# 05_RTC.net
KiCad netlist of a schematic drawn in Altium Designer
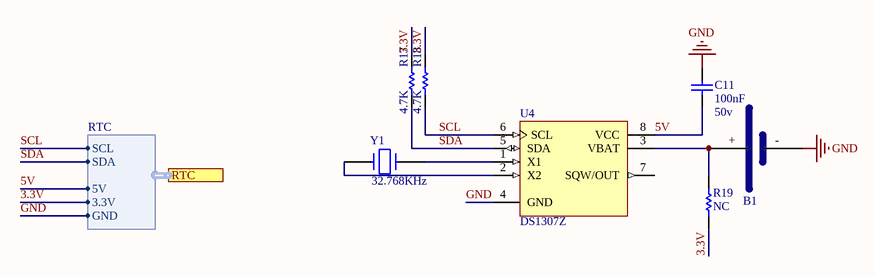
[diagram p0: [05] RTC.SchDoc]

(export (version "E")
  (design (tool "Eeschema 10.0.6"))
  (components
    (comp (ref "B1")
      (value "Littium Battery")
      (footprint "MY_RTC BAT SMD")
      (description "3V PC Littium Battery")
      (libsource (lib "Mylib Rev 4") (part "Battery"))
    )
    (comp (ref "C11")
      (value "100nF")
      (footprint "MY_0603")
      (description "None polar capacitor")
      (fields (field (name "ASID PART NUMBER") "C-AS") (field (name "VOLTE") "50v"))
      (libsource (lib "Mylib Rev 4") (part "Cap ceramic"))
    )
    (comp (ref "R17")
      (value "4.7K")
      (footprint "MY_0603")
      (description "Standard resistor")
      (fields (field (name "ASID PART NUMBER") "Res-AS"))
      (libsource (lib "Mylib Rev 4") (part "Res"))
    )
    (comp (ref "R18")
      (value "4.7K")
      (footprint "MY_0603")
      (description "Standard resistor")
      (fields (field (name "ASID PART NUMBER") "Res-AS"))
      (libsource (lib "Mylib Rev 4") (part "Res"))
    )
    (comp (ref "R19")
      (value "NC")
      (footprint "MY_0805")
      (description "resistor 1/4 wat")
      (libsource (lib "My Little Freind") (part "Res"))
    )
    (comp (ref "U4")
      (value "DS1307Z")
      (footprint "SOIC8N_N")
      (description "64 X 8 Serial Real-Time Clock")
      (fields (field (name "PUBLISHER") "Altium Limited"))
      (libsource (lib "Dallas Peripheral Real Time Clock") (part "DS1307Z"))
    )
    (comp (ref "Y1")
      (value "32.768KHz")
      (footprint "MY_RTC_Crystal")
      (description "Crystal")
      (fields (field (name "ASID PART NUMBER") "Crystal-AS"))
      (libsource (lib "Mylib Rev 4") (part "CRYSTAL"))
    )
  )
  (nets
    (net (code "2") (name "/3.3V") (class "Default")
      (node (ref "R17") (pin "1") (pinfunction "1_1") (pintype "passive"))
      (node (ref "R18") (pin "1") (pinfunction "1_1") (pintype "passive"))
      (node (ref "R19") (pin "2") (pinfunction "2_2") (pintype "passive"))
    )
    (net (code "3") (name "/5V") (class "Default")
      (node (ref "C11") (pin "1") (pinfunction "1_1") (pintype "passive"))
      (node (ref "U4") (pin "8") (pinfunction "VCC_8") (pintype "power_in"))
    )
    (net (code "4") (name "/SCL") (class "Default")
      (node (ref "R18") (pin "2") (pinfunction "2_2") (pintype "passive"))
      (node (ref "U4") (pin "6") (pinfunction "SCL_6") (pintype "input"))
    )
    (net (code "5") (name "/SDA") (class "Default")
      (node (ref "R17") (pin "2") (pinfunction "2_2") (pintype "passive"))
      (node (ref "U4") (pin "5") (pinfunction "SDA_5") (pintype "bidirectional"))
    )
    (net (code "7") (name "GND") (class "Default")
      (node (ref "B1") (pin "-") (pinfunction "-_-") (pintype "passive"))
      (node (ref "C11") (pin "2") (pinfunction "2_2") (pintype "passive"))
      (node (ref "U4") (pin "4") (pinfunction "GND_4") (pintype "power_in"))
    )
    (net (code "8") (name "Net-(U4-VBAT)") (class "Default")
      (node (ref "B1") (pin "+") (pinfunction "+_+") (pintype "passive"))
      (node (ref "R19") (pin "1") (pinfunction "1_1") (pintype "passive"))
      (node (ref "U4") (pin "3") (pinfunction "VBAT_3") (pintype "power_in"))
    )
    (net (code "9") (name "Net-(U4-X1)") (class "Default")
      (node (ref "U4") (pin "1") (pinfunction "X1_1") (pintype "input"))
      (node (ref "Y1") (pin "2") (pinfunction "2_2") (pintype "passive"))
    )
    (net (code "10") (name "Net-(U4-X2)") (class "Default")
      (node (ref "U4") (pin "2") (pinfunction "X2_2") (pintype "input"))
      (node (ref "Y1") (pin "1") (pinfunction "1_1") (pintype "passive"))
    )
    (net (code "11") (name "unconnected-(B1-Pad0)") (class "Default")
      (node (ref "B1") (pin "0") (pinfunction "0_0") (pintype "passive"))
    )
    (net (code "12") (name "unconnected-(U4-SQW{slash}OUT-Pad7)") (class "Default")
      (node (ref "U4") (pin "7") (pinfunction "SQW/OUT_7") (pintype "output"))
    )
  )
)
